# Nearness1u_PCB.net
KiCad netlist of a schematic drawn in EAGLE
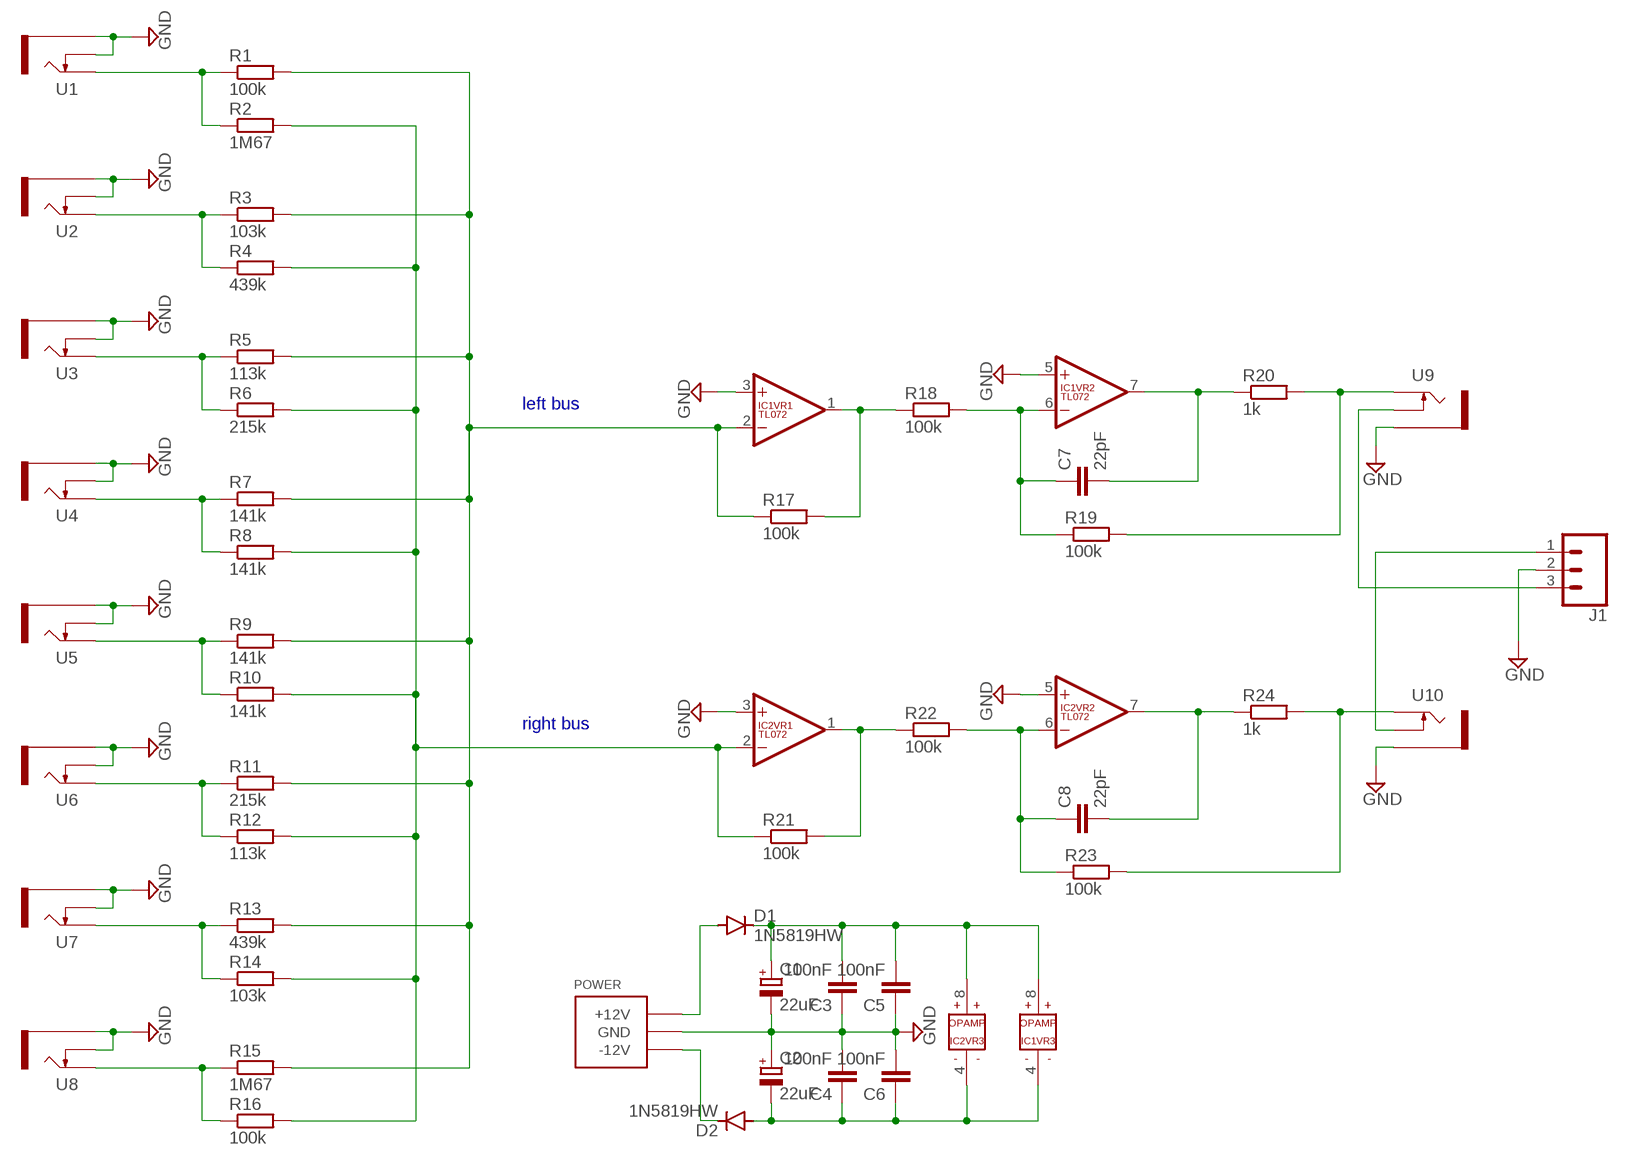
[diagram p0: schematic, sheet 1]

(export (version "E")
  (design (tool "Eeschema 10.0.6"))
  (components
    (comp (ref "C1")
      (value "22uF")
      (footprint "eagle-import:153CLV-0405")
      (libsource (lib "eagle-import") (part "CPOL-EU153CLV-0405"))
    )
    (comp (ref "C2")
      (value "22uF")
      (footprint "eagle-import:153CLV-0405")
      (libsource (lib "eagle-import") (part "CPOL-EU153CLV-0405"))
    )
    (comp (ref "C3")
      (value "100nF")
      (footprint "eagle-import:C0805")
      (libsource (lib "eagle-import") (part "C-EUC0805"))
    )
    (comp (ref "C4")
      (value "100nF")
      (footprint "eagle-import:C0805")
      (libsource (lib "eagle-import") (part "C-EUC0805"))
    )
    (comp (ref "C5")
      (value "100nF")
      (footprint "eagle-import:C0805")
      (libsource (lib "eagle-import") (part "C-EUC0805"))
    )
    (comp (ref "C6")
      (value "100nF")
      (footprint "eagle-import:C0805")
      (libsource (lib "eagle-import") (part "C-EUC0805"))
    )
    (comp (ref "C7")
      (value "22pF")
      (footprint "eagle-import:C0805")
      (libsource (lib "eagle-import") (part "C-EUC0805"))
    )
    (comp (ref "C8")
      (value "22pF")
      (footprint "eagle-import:C0805")
      (libsource (lib "eagle-import") (part "C-EUC0805"))
    )
    (comp (ref "D1")
      (value "1N5819HW")
      (footprint "eagle-import:SOD123")
      (libsource (lib "eagle-import") (part "DIODE-SOD123"))
    )
    (comp (ref "D2")
      (value "1N5819HW")
      (footprint "eagle-import:SOD123")
      (libsource (lib "eagle-import") (part "DIODE-SOD123"))
    )
    (comp (ref "IC1")
      (value "TL072")
      (footprint "eagle-import:SO08")
      (libsource (lib "eagle-import") (part "TL072"))
    )
    (comp (ref "IC2")
      (value "TL072")
      (footprint "eagle-import:SO08")
      (libsource (lib "eagle-import") (part "TL072"))
    )
    (comp (ref "J1")
      (value "CONN_03")
      (footprint "eagle-import:1X03")
      (libsource (lib "eagle-import") (part "CONN_03"))
    )
    (comp (ref "POWER")
      (value "POWER_SIMPLE")
      (footprint "eagle-import:2X05_SMT_HEADER")
      (libsource (lib "eagle-import") (part "POWER_SIMPLE"))
    )
    (comp (ref "R1")
      (value "100k")
      (footprint "eagle-import:R0805")
      (libsource (lib "eagle-import") (part "R-EU_R0805"))
    )
    (comp (ref "R2")
      (value "1M67")
      (footprint "eagle-import:R0805")
      (libsource (lib "eagle-import") (part "R-EU_R0805"))
    )
    (comp (ref "R3")
      (value "103k")
      (footprint "eagle-import:R0805")
      (libsource (lib "eagle-import") (part "R-EU_R0805"))
    )
    (comp (ref "R4")
      (value "439k")
      (footprint "eagle-import:R0805")
      (libsource (lib "eagle-import") (part "R-EU_R0805"))
    )
    (comp (ref "R5")
      (value "113k")
      (footprint "eagle-import:R0805")
      (libsource (lib "eagle-import") (part "R-EU_R0805"))
    )
    (comp (ref "R6")
      (value "215k")
      (footprint "eagle-import:R0805")
      (libsource (lib "eagle-import") (part "R-EU_R0805"))
    )
    (comp (ref "R7")
      (value "141k")
      (footprint "eagle-import:R0805")
      (libsource (lib "eagle-import") (part "R-EU_R0805"))
    )
    (comp (ref "R8")
      (value "141k")
      (footprint "eagle-import:R0805")
      (libsource (lib "eagle-import") (part "R-EU_R0805"))
    )
    (comp (ref "R9")
      (value "141k")
      (footprint "eagle-import:R0805")
      (libsource (lib "eagle-import") (part "R-EU_R0805"))
    )
    (comp (ref "R10")
      (value "141k")
      (footprint "eagle-import:R0805")
      (libsource (lib "eagle-import") (part "R-EU_R0805"))
    )
    (comp (ref "R11")
      (value "215k")
      (footprint "eagle-import:R0805")
      (libsource (lib "eagle-import") (part "R-EU_R0805"))
    )
    (comp (ref "R12")
      (value "113k")
      (footprint "eagle-import:R0805")
      (libsource (lib "eagle-import") (part "R-EU_R0805"))
    )
    (comp (ref "R13")
      (value "439k")
      (footprint "eagle-import:R0805")
      (libsource (lib "eagle-import") (part "R-EU_R0805"))
    )
    (comp (ref "R14")
      (value "103k")
      (footprint "eagle-import:R0805")
      (libsource (lib "eagle-import") (part "R-EU_R0805"))
    )
    (comp (ref "R15")
      (value "1M67")
      (footprint "eagle-import:R0805")
      (libsource (lib "eagle-import") (part "R-EU_R0805"))
    )
    (comp (ref "R16")
      (value "100k")
      (footprint "eagle-import:R0805")
      (libsource (lib "eagle-import") (part "R-EU_R0805"))
    )
    (comp (ref "R17")
      (value "100k")
      (footprint "eagle-import:R0805")
      (libsource (lib "eagle-import") (part "R-EU_R0805"))
    )
    (comp (ref "R18")
      (value "100k")
      (footprint "eagle-import:R0805")
      (libsource (lib "eagle-import") (part "R-EU_R0805"))
    )
    (comp (ref "R19")
      (value "100k")
      (footprint "eagle-import:R0805")
      (libsource (lib "eagle-import") (part "R-EU_R0805"))
    )
    (comp (ref "R20")
      (value "1k")
      (footprint "eagle-import:R0805")
      (libsource (lib "eagle-import") (part "R-EU_R0805"))
    )
    (comp (ref "R21")
      (value "100k")
      (footprint "eagle-import:R0805")
      (libsource (lib "eagle-import") (part "R-EU_R0805"))
    )
    (comp (ref "R22")
      (value "100k")
      (footprint "eagle-import:R0805")
      (libsource (lib "eagle-import") (part "R-EU_R0805"))
    )
    (comp (ref "R23")
      (value "100k")
      (footprint "eagle-import:R0805")
      (libsource (lib "eagle-import") (part "R-EU_R0805"))
    )
    (comp (ref "R24")
      (value "1k")
      (footprint "eagle-import:R0805")
      (libsource (lib "eagle-import") (part "R-EU_R0805"))
    )
    (comp (ref "U1")
      (value "THONKICONNNEW")
      (footprint "eagle-import:WQP-PJ301M-12_JACK")
      (libsource (lib "eagle-import") (part "THONKICONNNEW"))
    )
    (comp (ref "U2")
      (value "THONKICONNNEW")
      (footprint "eagle-import:WQP-PJ301M-12_JACK")
      (libsource (lib "eagle-import") (part "THONKICONNNEW"))
    )
    (comp (ref "U3")
      (value "THONKICONNNEW")
      (footprint "eagle-import:WQP-PJ301M-12_JACK")
      (libsource (lib "eagle-import") (part "THONKICONNNEW"))
    )
    (comp (ref "U4")
      (value "THONKICONNNEW")
      (footprint "eagle-import:WQP-PJ301M-12_JACK")
      (libsource (lib "eagle-import") (part "THONKICONNNEW"))
    )
    (comp (ref "U5")
      (value "THONKICONNNEW")
      (footprint "eagle-import:WQP-PJ301M-12_JACK")
      (libsource (lib "eagle-import") (part "THONKICONNNEW"))
    )
    (comp (ref "U6")
      (value "THONKICONNNEW")
      (footprint "eagle-import:WQP-PJ301M-12_JACK")
      (libsource (lib "eagle-import") (part "THONKICONNNEW"))
    )
    (comp (ref "U7")
      (value "THONKICONNNEW")
      (footprint "eagle-import:WQP-PJ301M-12_JACK")
      (libsource (lib "eagle-import") (part "THONKICONNNEW"))
    )
    (comp (ref "U8")
      (value "THONKICONNNEW")
      (footprint "eagle-import:WQP-PJ301M-12_JACK")
      (libsource (lib "eagle-import") (part "THONKICONNNEW"))
    )
    (comp (ref "U9")
      (value "THONKICONNNEW")
      (footprint "eagle-import:WQP-PJ301M-12_JACK")
      (libsource (lib "eagle-import") (part "THONKICONNNEW"))
    )
    (comp (ref "U10")
      (value "THONKICONNNEW")
      (footprint "eagle-import:WQP-PJ301M-12_JACK")
      (libsource (lib "eagle-import") (part "THONKICONNNEW"))
    )
  )
  (nets
    (net (code "1") (name "GND") (class "Default")
      (node (ref "C1") (pin "-") (pinfunction "-_-") (pintype "passive"))
      (node (ref "C2") (pin "+") (pinfunction "+_+") (pintype "passive"))
      (node (ref "C3") (pin "1") (pinfunction "1_1") (pintype "passive"))
      (node (ref "C4") (pin "2") (pinfunction "2_2") (pintype "passive"))
      (node (ref "C5") (pin "1") (pinfunction "1_1") (pintype "passive"))
      (node (ref "C6") (pin "2") (pinfunction "2_2") (pintype "passive"))
      (node (ref "IC1") (pin "3") (pinfunction "+IN_3") (pintype "input"))
      (node (ref "IC1") (pin "5") (pinfunction "+IN_5") (pintype "input"))
      (node (ref "IC2") (pin "3") (pinfunction "+IN_3") (pintype "input"))
      (node (ref "IC2") (pin "5") (pinfunction "+IN_5") (pintype "input"))
      (node (ref "J1") (pin "2") (pinfunction "2_2") (pintype "passive"))
      (node (ref "POWER") (pin "3") (pinfunction "GND_3") (pintype "bidirectional"))
      (node (ref "POWER") (pin "4") (pinfunction "GND_4") (pintype "bidirectional"))
      (node (ref "POWER") (pin "5") (pinfunction "GND_5") (pintype "bidirectional"))
      (node (ref "POWER") (pin "6") (pinfunction "GND_6") (pintype "bidirectional"))
      (node (ref "POWER") (pin "7") (pinfunction "GND_7") (pintype "bidirectional"))
      (node (ref "POWER") (pin "8") (pinfunction "GND_8") (pintype "bidirectional"))
      (node (ref "U1") (pin "P$2_SWITCH") (pinfunction "SWITCH_P$2_SWITCH") (pintype "passive"))
      (node (ref "U1") (pin "P$3_SLEEVE") (pinfunction "SLEEVE_P$3_SLEEVE") (pintype "passive"))
      (node (ref "U10") (pin "P$3_SLEEVE") (pinfunction "SLEEVE_P$3_SLEEVE") (pintype "passive"))
      (node (ref "U2") (pin "P$2_SWITCH") (pinfunction "SWITCH_P$2_SWITCH") (pintype "passive"))
      (node (ref "U2") (pin "P$3_SLEEVE") (pinfunction "SLEEVE_P$3_SLEEVE") (pintype "passive"))
      (node (ref "U3") (pin "P$2_SWITCH") (pinfunction "SWITCH_P$2_SWITCH") (pintype "passive"))
      (node (ref "U3") (pin "P$3_SLEEVE") (pinfunction "SLEEVE_P$3_SLEEVE") (pintype "passive"))
      (node (ref "U4") (pin "P$2_SWITCH") (pinfunction "SWITCH_P$2_SWITCH") (pintype "passive"))
      (node (ref "U4") (pin "P$3_SLEEVE") (pinfunction "SLEEVE_P$3_SLEEVE") (pintype "passive"))
      (node (ref "U5") (pin "P$2_SWITCH") (pinfunction "SWITCH_P$2_SWITCH") (pintype "passive"))
      (node (ref "U5") (pin "P$3_SLEEVE") (pinfunction "SLEEVE_P$3_SLEEVE") (pintype "passive"))
      (node (ref "U6") (pin "P$2_SWITCH") (pinfunction "SWITCH_P$2_SWITCH") (pintype "passive"))
      (node (ref "U6") (pin "P$3_SLEEVE") (pinfunction "SLEEVE_P$3_SLEEVE") (pintype "passive"))
      (node (ref "U7") (pin "P$2_SWITCH") (pinfunction "SWITCH_P$2_SWITCH") (pintype "passive"))
      (node (ref "U7") (pin "P$3_SLEEVE") (pinfunction "SLEEVE_P$3_SLEEVE") (pintype "passive"))
      (node (ref "U8") (pin "P$2_SWITCH") (pinfunction "SWITCH_P$2_SWITCH") (pintype "passive"))
      (node (ref "U8") (pin "P$3_SLEEVE") (pinfunction "SLEEVE_P$3_SLEEVE") (pintype "passive"))
      (node (ref "U9") (pin "P$3_SLEEVE") (pinfunction "SLEEVE_P$3_SLEEVE") (pintype "passive"))
    )
    (net (code "2") (name "Net-(D1-PadA)") (class "Default")
      (node (ref "D1") (pin "A") (pinfunction "A_A") (pintype "passive"))
      (node (ref "POWER") (pin "10") (pinfunction "+12V_10") (pintype "bidirectional"))
      (node (ref "POWER") (pin "9") (pinfunction "+12V_9") (pintype "bidirectional"))
    )
    (net (code "3") (name "Net-(D2-PadC)") (class "Default")
      (node (ref "D2") (pin "C") (pinfunction "C_C") (pintype "passive"))
      (node (ref "POWER") (pin "1") (pinfunction "-12V_1") (pintype "bidirectional"))
      (node (ref "POWER") (pin "2") (pinfunction "-12V_2") (pintype "bidirectional"))
    )
    (net (code "4") (name "Net-(IC1A--IN)") (class "Default")
      (node (ref "IC1") (pin "2") (pinfunction "-IN_2") (pintype "input"))
      (node (ref "R1") (pin "2") (pinfunction "2_2") (pintype "passive"))
      (node (ref "R11") (pin "2") (pinfunction "2_2") (pintype "passive"))
      (node (ref "R13") (pin "2") (pinfunction "2_2") (pintype "passive"))
      (node (ref "R15") (pin "2") (pinfunction "2_2") (pintype "passive"))
      (node (ref "R17") (pin "1") (pinfunction "1_1") (pintype "passive"))
      (node (ref "R3") (pin "2") (pinfunction "2_2") (pintype "passive"))
      (node (ref "R5") (pin "2") (pinfunction "2_2") (pintype "passive"))
      (node (ref "R7") (pin "2") (pinfunction "2_2") (pintype "passive"))
      (node (ref "R9") (pin "2") (pinfunction "2_2") (pintype "passive"))
    )
    (net (code "5") (name "Net-(IC1A-OUT)") (class "Default")
      (node (ref "IC1") (pin "1") (pinfunction "OUT_1") (pintype "output"))
      (node (ref "R17") (pin "2") (pinfunction "2_2") (pintype "passive"))
      (node (ref "R18") (pin "1") (pinfunction "1_1") (pintype "passive"))
    )
    (net (code "6") (name "Net-(IC1B--IN)") (class "Default")
      (node (ref "C7") (pin "1") (pinfunction "1_1") (pintype "passive"))
      (node (ref "IC1") (pin "6") (pinfunction "-IN_6") (pintype "input"))
      (node (ref "R18") (pin "2") (pinfunction "2_2") (pintype "passive"))
      (node (ref "R19") (pin "1") (pinfunction "1_1") (pintype "passive"))
    )
    (net (code "7") (name "Net-(IC1B-OUT)") (class "Default")
      (node (ref "C7") (pin "2") (pinfunction "2_2") (pintype "passive"))
      (node (ref "IC1") (pin "7") (pinfunction "OUT_7") (pintype "output"))
      (node (ref "R20") (pin "1") (pinfunction "1_1") (pintype "passive"))
    )
    (net (code "8") (name "Net-(IC1C-V+)") (class "Default")
      (node (ref "C1") (pin "+") (pinfunction "+_+") (pintype "passive"))
      (node (ref "C3") (pin "2") (pinfunction "2_2") (pintype "passive"))
      (node (ref "C5") (pin "2") (pinfunction "2_2") (pintype "passive"))
      (node (ref "D1") (pin "C") (pinfunction "C_C") (pintype "passive"))
      (node (ref "IC1") (pin "8") (pinfunction "V+_8") (pintype "power_in"))
      (node (ref "IC2") (pin "8") (pinfunction "V+_8") (pintype "power_in"))
    )
    (net (code "9") (name "Net-(IC1C-V-)") (class "Default")
      (node (ref "C2") (pin "-") (pinfunction "-_-") (pintype "passive"))
      (node (ref "C4") (pin "1") (pinfunction "1_1") (pintype "passive"))
      (node (ref "C6") (pin "1") (pinfunction "1_1") (pintype "passive"))
      (node (ref "D2") (pin "A") (pinfunction "A_A") (pintype "passive"))
      (node (ref "IC1") (pin "4") (pinfunction "V-_4") (pintype "power_in"))
      (node (ref "IC2") (pin "4") (pinfunction "V-_4") (pintype "power_in"))
    )
    (net (code "10") (name "Net-(IC2A--IN)") (class "Default")
      (node (ref "IC2") (pin "2") (pinfunction "-IN_2") (pintype "input"))
      (node (ref "R10") (pin "2") (pinfunction "2_2") (pintype "passive"))
      (node (ref "R12") (pin "2") (pinfunction "2_2") (pintype "passive"))
      (node (ref "R14") (pin "2") (pinfunction "2_2") (pintype "passive"))
      (node (ref "R16") (pin "2") (pinfunction "2_2") (pintype "passive"))
      (node (ref "R2") (pin "2") (pinfunction "2_2") (pintype "passive"))
      (node (ref "R21") (pin "1") (pinfunction "1_1") (pintype "passive"))
      (node (ref "R4") (pin "2") (pinfunction "2_2") (pintype "passive"))
      (node (ref "R6") (pin "2") (pinfunction "2_2") (pintype "passive"))
      (node (ref "R8") (pin "2") (pinfunction "2_2") (pintype "passive"))
    )
    (net (code "11") (name "Net-(IC2A-OUT)") (class "Default")
      (node (ref "IC2") (pin "1") (pinfunction "OUT_1") (pintype "output"))
      (node (ref "R21") (pin "2") (pinfunction "2_2") (pintype "passive"))
      (node (ref "R22") (pin "1") (pinfunction "1_1") (pintype "passive"))
    )
    (net (code "12") (name "Net-(IC2B--IN)") (class "Default")
      (node (ref "C8") (pin "1") (pinfunction "1_1") (pintype "passive"))
      (node (ref "IC2") (pin "6") (pinfunction "-IN_6") (pintype "input"))
      (node (ref "R22") (pin "2") (pinfunction "2_2") (pintype "passive"))
      (node (ref "R23") (pin "1") (pinfunction "1_1") (pintype "passive"))
    )
    (net (code "13") (name "Net-(IC2B-OUT)") (class "Default")
      (node (ref "C8") (pin "2") (pinfunction "2_2") (pintype "passive"))
      (node (ref "IC2") (pin "7") (pinfunction "OUT_7") (pintype "output"))
      (node (ref "R24") (pin "1") (pinfunction "1_1") (pintype "passive"))
    )
    (net (code "14") (name "Net-(U1-TIP)") (class "Default")
      (node (ref "R1") (pin "1") (pinfunction "1_1") (pintype "passive"))
      (node (ref "R2") (pin "1") (pinfunction "1_1") (pintype "passive"))
      (node (ref "U1") (pin "P$1_TIP") (pinfunction "TIP_P$1_TIP") (pintype "passive"))
    )
    (net (code "15") (name "Net-(U2-TIP)") (class "Default")
      (node (ref "R3") (pin "1") (pinfunction "1_1") (pintype "passive"))
      (node (ref "R4") (pin "1") (pinfunction "1_1") (pintype "passive"))
      (node (ref "U2") (pin "P$1_TIP") (pinfunction "TIP_P$1_TIP") (pintype "passive"))
    )
    (net (code "16") (name "Net-(U3-TIP)") (class "Default")
      (node (ref "R5") (pin "1") (pinfunction "1_1") (pintype "passive"))
      (node (ref "R6") (pin "1") (pinfunction "1_1") (pintype "passive"))
      (node (ref "U3") (pin "P$1_TIP") (pinfunction "TIP_P$1_TIP") (pintype "passive"))
    )
    (net (code "17") (name "Net-(U4-TIP)") (class "Default")
      (node (ref "R7") (pin "1") (pinfunction "1_1") (pintype "passive"))
      (node (ref "R8") (pin "1") (pinfunction "1_1") (pintype "passive"))
      (node (ref "U4") (pin "P$1_TIP") (pinfunction "TIP_P$1_TIP") (pintype "passive"))
    )
    (net (code "18") (name "Net-(U5-TIP)") (class "Default")
      (node (ref "R10") (pin "1") (pinfunction "1_1") (pintype "passive"))
      (node (ref "R9") (pin "1") (pinfunction "1_1") (pintype "passive"))
      (node (ref "U5") (pin "P$1_TIP") (pinfunction "TIP_P$1_TIP") (pintype "passive"))
    )
    (net (code "19") (name "Net-(U6-TIP)") (class "Default")
      (node (ref "R11") (pin "1") (pinfunction "1_1") (pintype "passive"))
      (node (ref "R12") (pin "1") (pinfunction "1_1") (pintype "passive"))
      (node (ref "U6") (pin "P$1_TIP") (pinfunction "TIP_P$1_TIP") (pintype "passive"))
    )
    (net (code "20") (name "Net-(U7-TIP)") (class "Default")
      (node (ref "R13") (pin "1") (pinfunction "1_1") (pintype "passive"))
      (node (ref "R14") (pin "1") (pinfunction "1_1") (pintype "passive"))
      (node (ref "U7") (pin "P$1_TIP") (pinfunction "TIP_P$1_TIP") (pintype "passive"))
    )
    (net (code "21") (name "Net-(U8-TIP)") (class "Default")
      (node (ref "R15") (pin "1") (pinfunction "1_1") (pintype "passive"))
      (node (ref "R16") (pin "1") (pinfunction "1_1") (pintype "passive"))
      (node (ref "U8") (pin "P$1_TIP") (pinfunction "TIP_P$1_TIP") (pintype "passive"))
    )
    (net (code "22") (name "Net-(U9-SWITCH)") (class "Default")
      (node (ref "J1") (pin "3") (pinfunction "3_3") (pintype "passive"))
      (node (ref "U9") (pin "P$2_SWITCH") (pinfunction "SWITCH_P$2_SWITCH") (pintype "passive"))
    )
    (net (code "23") (name "Net-(U9-TIP)") (class "Default")
      (node (ref "R19") (pin "2") (pinfunction "2_2") (pintype "passive"))
      (node (ref "R20") (pin "2") (pinfunction "2_2") (pintype "passive"))
      (node (ref "U9") (pin "P$1_TIP") (pinfunction "TIP_P$1_TIP") (pintype "passive"))
    )
    (net (code "24") (name "Net-(U10-SWITCH)") (class "Default")
      (node (ref "J1") (pin "1") (pinfunction "1_1") (pintype "passive"))
      (node (ref "U10") (pin "P$2_SWITCH") (pinfunction "SWITCH_P$2_SWITCH") (pintype "passive"))
    )
    (net (code "25") (name "Net-(U10-TIP)") (class "Default")
      (node (ref "R23") (pin "2") (pinfunction "2_2") (pintype "passive"))
      (node (ref "R24") (pin "2") (pinfunction "2_2") (pintype "passive"))
      (node (ref "U10") (pin "P$1_TIP") (pinfunction "TIP_P$1_TIP") (pintype "passive"))
    )
  )
)
